# MAX86141_HEG_MINI.net
KiCad netlist of a schematic drawn in EAGLE
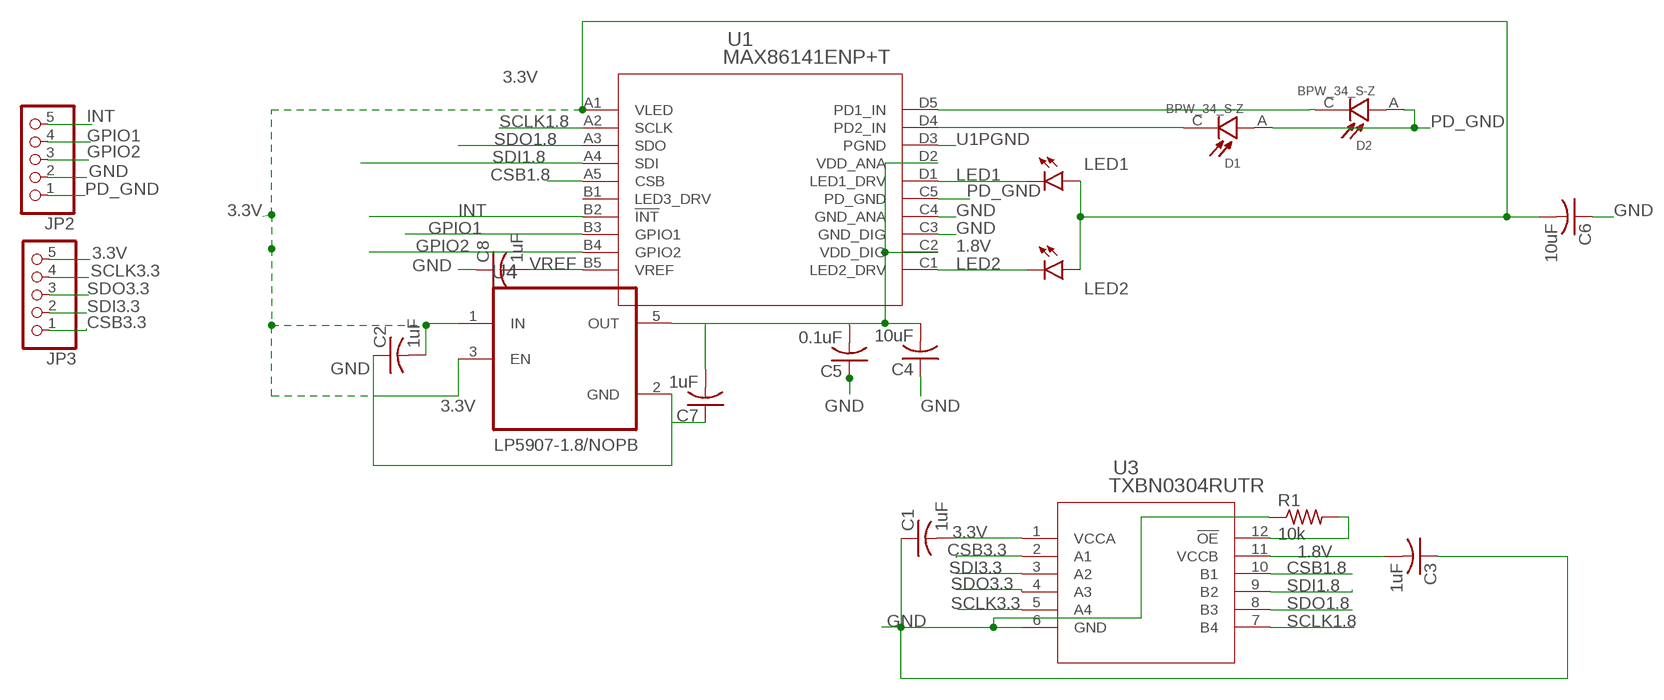
[diagram p0: schematic, sheet 1]

(export (version "E")
  (design (tool "Eeschema 10.0.6"))
  (components
    (comp (ref "C1")
      (value "1uF")
      (footprint "eagle-import:C0402")
      (libsource (lib "eagle-import") (part "C-USC0402"))
    )
    (comp (ref "C2")
      (value "1uF")
      (footprint "eagle-import:C0402")
      (libsource (lib "eagle-import") (part "C-USC0402"))
    )
    (comp (ref "C3")
      (value "1uF")
      (footprint "eagle-import:C0402")
      (libsource (lib "eagle-import") (part "C-USC0402"))
    )
    (comp (ref "C4")
      (value "10uF")
      (footprint "eagle-import:C0402")
      (libsource (lib "eagle-import") (part "C-USC0402"))
    )
    (comp (ref "C5")
      (value "0.1uF")
      (footprint "eagle-import:C0402")
      (libsource (lib "eagle-import") (part "C-USC0402"))
    )
    (comp (ref "C6")
      (value "10uF")
      (footprint "eagle-import:C0402")
      (libsource (lib "eagle-import") (part "C-USC0402"))
    )
    (comp (ref "C7")
      (value "1uF")
      (footprint "eagle-import:C0402")
      (libsource (lib "eagle-import") (part "C-USC0402"))
    )
    (comp (ref "C8")
      (value "1uF")
      (footprint "eagle-import:C0402")
      (libsource (lib "eagle-import") (part "C-USC0402"))
    )
    (comp (ref "D1")
      (value "BPW_34_S-Z")
      (footprint "eagle-import:DIO_BPW_34_S-Z")
      (fields
        (field (name "DIGI-KEY_PART_NUMBER") "475-2659-1-ND")
        (field (name "MF") "OSRAM Opto")
        (field (name "MP") "BPW 34 S-Z")
      )
      (libsource (lib "eagle-import") (part "BPW_34_S-Z"))
    )
    (comp (ref "D2")
      (value "BPW_34_S-Z")
      (footprint "eagle-import:DIO_BPW_34_S-Z")
      (fields
        (field (name "DIGI-KEY_PART_NUMBER") "475-2659-1-ND")
        (field (name "MF") "OSRAM Opto")
        (field (name "MP") "BPW 34 S-Z")
      )
      (libsource (lib "eagle-import") (part "BPW_34_S-Z"))
    )
    (comp (ref "JP2")
      (value "PINHD-1X5")
      (footprint "eagle-import:1X05")
      (libsource (lib "eagle-import") (part "PINHD-1X5"))
    )
    (comp (ref "JP3")
      (value "PINHD-1X5")
      (footprint "eagle-import:1X05")
      (libsource (lib "eagle-import") (part "PINHD-1X5"))
    )
    (comp (ref "LED1")
      (value "LEDCHIPLED_1206")
      (footprint "eagle-import:CHIPLED_1206")
      (libsource (lib "eagle-import") (part "LEDCHIPLED_1206"))
    )
    (comp (ref "LED2")
      (value "LEDCHIPLED_1206")
      (footprint "eagle-import:CHIPLED_1206")
      (libsource (lib "eagle-import") (part "LEDCHIPLED_1206"))
    )
    (comp (ref "R1")
      (value "10k")
      (footprint "eagle-import:R0402")
      (libsource (lib "eagle-import") (part "R-US_R0402"))
    )
    (comp (ref "U1")
      (value "MAX86141ENP+T")
      (footprint "eagle-import:21-100134A_20")
      (libsource (lib "eagle-import") (part "MAX86141ENP+T"))
    )
    (comp (ref "U3")
      (value "TXBN0304RUTR")
      (footprint "eagle-import:RUT12")
      (libsource (lib "eagle-import") (part "TXBN0304RUTR"))
    )
    (comp (ref "U4")
      (value "LP5907MFX-3.3/NOPB")
      (footprint "eagle-import:SOT95P280X145-5N")
      (fields (field (name "MF") "Texas Instruments"))
      (libsource (lib "eagle-import") (part "LP5907MFX-3.3/NOPB"))
    )
  )
  (nets
    (net (code "1") (name "/1.8V") (class "Default")
      (node (ref "C3") (pin "2") (pinfunction "2_2") (pintype "passive"))
      (node (ref "C4") (pin "2") (pinfunction "2_2") (pintype "passive"))
      (node (ref "C5") (pin "2") (pinfunction "2_2") (pintype "passive"))
      (node (ref "C7") (pin "2") (pinfunction "2_2") (pintype "passive"))
      (node (ref "U1") (pin "C2") (pinfunction "VDD_DIG_C2") (pintype "power_in"))
      (node (ref "U1") (pin "D2") (pinfunction "VDD_ANA_D2") (pintype "power_in"))
      (node (ref "U3") (pin "11") (pinfunction "VCCB_11") (pintype "power_in"))
      (node (ref "U4") (pin "5") (pinfunction "OUT_5") (pintype "output"))
    )
    (net (code "2") (name "/3.3V") (class "Default")
      (node (ref "C1") (pin "2") (pinfunction "2_2") (pintype "passive"))
      (node (ref "C2") (pin "2") (pinfunction "2_2") (pintype "passive"))
      (node (ref "C6") (pin "2") (pinfunction "2_2") (pintype "passive"))
      (node (ref "JP3") (pin "5") (pinfunction "5_5") (pintype "passive"))
      (node (ref "LED1") (pin "A") (pinfunction "A_A") (pintype "passive"))
      (node (ref "LED2") (pin "A") (pinfunction "A_A") (pintype "passive"))
      (node (ref "U1") (pin "A1") (pinfunction "VLED_A1") (pintype "passive"))
      (node (ref "U3") (pin "1") (pinfunction "VCCA_1") (pintype "power_in"))
      (node (ref "U4") (pin "1") (pinfunction "IN_1") (pintype "input"))
      (node (ref "U4") (pin "3") (pinfunction "EN_3") (pintype "input"))
    )
    (net (code "3") (name "/CSB1.8") (class "Default")
      (node (ref "U1") (pin "A5") (pinfunction "CSB_A5") (pintype "passive"))
      (node (ref "U3") (pin "10") (pinfunction "B1_10") (pintype "bidirectional"))
    )
    (net (code "4") (name "/CSB3.3") (class "Default")
      (node (ref "JP3") (pin "1") (pinfunction "1_1") (pintype "passive"))
      (node (ref "U3") (pin "2") (pinfunction "A1_2") (pintype "bidirectional"))
    )
    (net (code "5") (name "/GND") (class "Default")
      (node (ref "C1") (pin "1") (pinfunction "1_1") (pintype "passive"))
      (node (ref "C2") (pin "1") (pinfunction "1_1") (pintype "passive"))
      (node (ref "C3") (pin "1") (pinfunction "1_1") (pintype "passive"))
      (node (ref "C4") (pin "1") (pinfunction "1_1") (pintype "passive"))
      (node (ref "C5") (pin "1") (pinfunction "1_1") (pintype "passive"))
      (node (ref "C6") (pin "1") (pinfunction "1_1") (pintype "passive"))
      (node (ref "C7") (pin "1") (pinfunction "1_1") (pintype "passive"))
      (node (ref "C8") (pin "1") (pinfunction "1_1") (pintype "passive"))
      (node (ref "JP2") (pin "2") (pinfunction "2_2") (pintype "passive"))
      (node (ref "R1") (pin "1") (pinfunction "1_1") (pintype "passive"))
      (node (ref "U1") (pin "C3") (pinfunction "GND_DIG_C3") (pintype "passive"))
      (node (ref "U1") (pin "C4") (pinfunction "GND_ANA_C4") (pintype "passive"))
      (node (ref "U3") (pin "6") (pinfunction "GND_6") (pintype "power_in"))
      (node (ref "U4") (pin "2") (pinfunction "GND_2") (pintype "power_in"))
    )
    (net (code "6") (name "/GPIO1") (class "Default")
      (node (ref "JP2") (pin "4") (pinfunction "4_4") (pintype "passive"))
      (node (ref "U1") (pin "B3") (pinfunction "GPIO1_B3") (pintype "bidirectional"))
    )
    (net (code "7") (name "/GPIO2") (class "Default")
      (node (ref "JP2") (pin "3") (pinfunction "3_3") (pintype "passive"))
      (node (ref "U1") (pin "B4") (pinfunction "GPIO2_B4") (pintype "bidirectional"))
    )
    (net (code "8") (name "/INT") (class "Default")
      (node (ref "JP2") (pin "5") (pinfunction "5_5") (pintype "passive"))
      (node (ref "U1") (pin "B2") (pinfunction "~{INT}_B2") (pintype "passive"))
    )
    (net (code "9") (name "/LED1") (class "Default")
      (node (ref "LED1") (pin "C") (pinfunction "C_C") (pintype "passive"))
      (node (ref "U1") (pin "D1") (pinfunction "LED1_DRV_D1") (pintype "bidirectional"))
    )
    (net (code "10") (name "/LED2") (class "Default")
      (node (ref "LED2") (pin "C") (pinfunction "C_C") (pintype "passive"))
      (node (ref "U1") (pin "C1") (pinfunction "LED2_DRV_C1") (pintype "bidirectional"))
    )
    (net (code "11") (name "/PD_GND") (class "Default")
      (node (ref "D1") (pin "A") (pinfunction "A_A") (pintype "passive"))
      (node (ref "D2") (pin "A") (pinfunction "A_A") (pintype "passive"))
      (node (ref "JP2") (pin "1") (pinfunction "1_1") (pintype "passive"))
      (node (ref "U1") (pin "C5") (pinfunction "PD_GND_C5") (pintype "passive"))
    )
    (net (code "12") (name "/SCLK1.8") (class "Default")
      (node (ref "U1") (pin "A2") (pinfunction "SCLK_A2") (pintype "passive"))
      (node (ref "U3") (pin "7") (pinfunction "B4_7") (pintype "bidirectional"))
    )
    (net (code "13") (name "/SCLK3.3") (class "Default")
      (node (ref "JP3") (pin "4") (pinfunction "4_4") (pintype "passive"))
      (node (ref "U3") (pin "5") (pinfunction "A4_5") (pintype "bidirectional"))
    )
    (net (code "14") (name "/SDI1.8") (class "Default")
      (node (ref "U1") (pin "A4") (pinfunction "SDI_A4") (pintype "passive"))
      (node (ref "U3") (pin "9") (pinfunction "B2_9") (pintype "bidirectional"))
    )
    (net (code "15") (name "/SDI3.3") (class "Default")
      (node (ref "JP3") (pin "2") (pinfunction "2_2") (pintype "passive"))
      (node (ref "U3") (pin "3") (pinfunction "A2_3") (pintype "bidirectional"))
    )
    (net (code "16") (name "/SDO1.8") (class "Default")
      (node (ref "U1") (pin "A3") (pinfunction "SDO_A3") (pintype "passive"))
      (node (ref "U3") (pin "8") (pinfunction "B3_8") (pintype "bidirectional"))
    )
    (net (code "17") (name "/SDO3.3") (class "Default")
      (node (ref "JP3") (pin "3") (pinfunction "3_3") (pintype "passive"))
      (node (ref "U3") (pin "4") (pinfunction "A3_4") (pintype "bidirectional"))
    )
    (net (code "18") (name "/U1PGND") (class "Default")
      (node (ref "U1") (pin "D3") (pinfunction "PGND_D3") (pintype "passive"))
    )
    (net (code "19") (name "/VREF") (class "Default")
      (node (ref "C8") (pin "2") (pinfunction "2_2") (pintype "passive"))
      (node (ref "U1") (pin "B5") (pinfunction "VREF_B5") (pintype "power_in"))
    )
    (net (code "20") (name "Net-(U1-PD1_IN)") (class "Default")
      (node (ref "D2") (pin "C") (pinfunction "C_C") (pintype "passive"))
      (node (ref "U1") (pin "D5") (pinfunction "PD1_IN_D5") (pintype "bidirectional"))
    )
    (net (code "21") (name "Net-(U1-PD2_IN)") (class "Default")
      (node (ref "D1") (pin "C") (pinfunction "C_C") (pintype "passive"))
      (node (ref "U1") (pin "D4") (pinfunction "PD2_IN_D4") (pintype "bidirectional"))
    )
    (net (code "22") (name "Net-(U3-~{OE})") (class "Default")
      (node (ref "R1") (pin "2") (pinfunction "2_2") (pintype "passive"))
      (node (ref "U3") (pin "12") (pinfunction "~{OE}_12") (pintype "input"))
    )
    (net (code "23") (name "unconnected-(U1-LED3_DRV-PadB1)") (class "Default")
      (node (ref "U1") (pin "B1") (pinfunction "LED3_DRV_B1") (pintype "bidirectional"))
    )
  )
)
